# Power_Protection_DigitalAndAnalogInterfa.net
KiCad netlist of a schematic drawn in Altium Designer
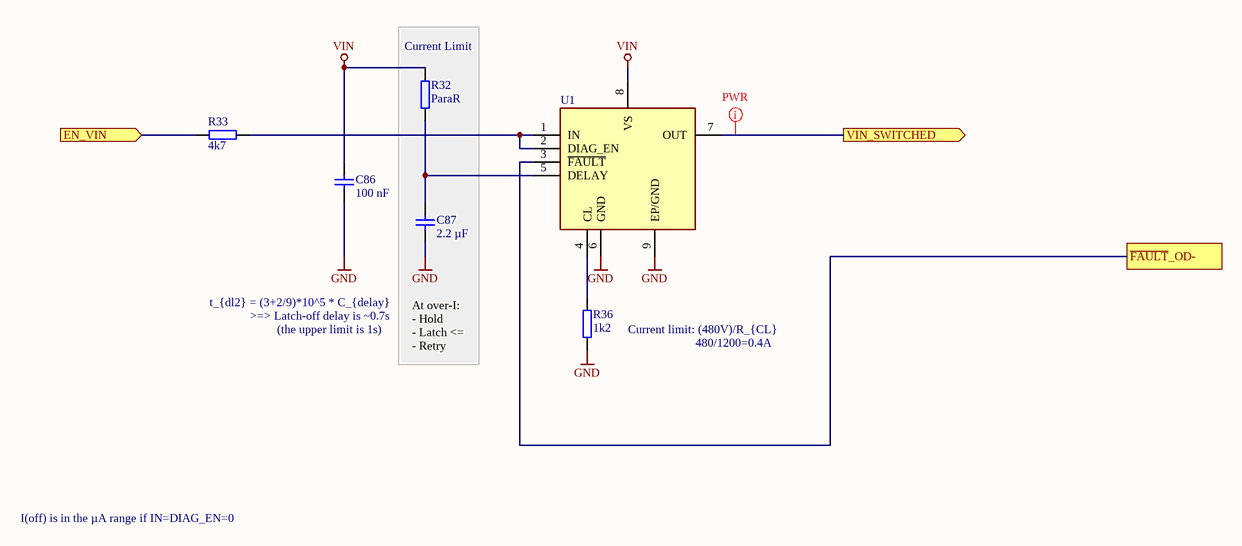
[diagram p0: Power_Protection_DigitalAndAnalogInterfaces.SchDoc]

(export (version "E")
  (design (tool "Eeschema 10.0.6"))
  (components
    (comp (ref "C86")
      (value "100 nF")
      (footprint "C_0603_TE")
      (description "Generic capacitor")
      (fields
        (field (name "MANUFACTURER PART NUMBER") "UZgen_C_0603_100nF_50V_X7R")
        (field (name "MANUFACTURER") "UZgen")
        (field (name "CREATED FROM") "AGeiger")
      )
      (libsource (lib "user") (part "CAP-NP"))
    )
    (comp (ref "C87")
      (value "2.2 µF")
      (footprint "C_0603_TE")
      (description "Generic capacitor")
      (fields
        (field (name "MANUFACTURER PART NUMBER") "UZgen_C_0603_2.2uF_50V_X7R")
        (field (name "MANUFACTURER") "UZgen")
        (field (name "CREATED FROM") "UZgenTool")
      )
      (libsource (lib "user") (part "CAP-NP"))
    )
    (comp (ref "R32")
      (value "ParaR")
      (footprint "R_0603_TE")
      (description "Generic resistor (parametric)")
      (fields
        (field (name "MANUFACTURER PART NUMBER") "UZgen_R_0603_ParaR")
        (field (name "MANUFACTURER") "UZgen")
        (field (name "CREATED FROM") "UZgenTool")
      )
      (libsource (lib "user") (part "RES"))
    )
    (comp (ref "R33")
      (value "4k7")
      (footprint "R_0603_TE")
      (description "Generic resistor")
      (fields
        (field (name "MANUFACTURER PART NUMBER") "UZgen_R_0603_4k7")
        (field (name "MANUFACTURER") "UZgen")
        (field (name "CREATED FROM") "UZgenTool")
      )
      (libsource (lib "user") (part "RES"))
    )
    (comp (ref "R36")
      (value "1k2")
      (footprint "R_0603_TE")
      (description "Generic resistor")
      (fields
        (field (name "MANUFACTURER PART NUMBER") "UZgen_R_0603_1k2")
        (field (name "MANUFACTURER") "UZgen")
        (field (name "CREATED FROM") "UZgenTool")
      )
      (libsource (lib "user") (part "RES"))
    )
    (comp (ref "U1")
      (value "TPS1H000AQDGNRQ1")
      (footprint "SOP65P490X110-9N")
      (fields
        (field (name "MANUFACTURER") "Texas Instruments")
        (field (name "LCSC PART NUMBER") "C2653764")
        (field (name "CREATED FROM") "FRosner")
      )
      (libsource (lib "user") (part "TPS1H000AQDGNRQ1"))
    )
  )
  (nets
    (net (code "1") (name "/EN_VIN") (class "Default")
      (node (ref "R33") (pin "1") (pinfunction "1_1") (pintype "passive"))
    )
    (net (code "2") (name "/VIN_SWITCHED") (class "Default")
      (node (ref "U1") (pin "7") (pinfunction "OUT_7") (pintype "passive"))
    )
    (net (code "3") (name "/~{FAULT}_OD-") (class "Default")
      (node (ref "U1") (pin "3") (pinfunction "~{FAULT}_3") (pintype "passive"))
    )
    (net (code "4") (name "GND") (class "Default")
      (node (ref "C86") (pin "1") (pinfunction "1_1") (pintype "passive"))
      (node (ref "C87") (pin "1") (pinfunction "1_1") (pintype "passive"))
      (node (ref "R36") (pin "1") (pinfunction "1_1") (pintype "passive"))
      (node (ref "U1") (pin "6") (pinfunction "GND_6") (pintype "passive"))
      (node (ref "U1") (pin "9") (pinfunction "EP/GND_9") (pintype "passive"))
    )
    (net (code "5") (name "Net-(U1-CL)") (class "Default")
      (node (ref "R36") (pin "2") (pinfunction "2_2") (pintype "passive"))
      (node (ref "U1") (pin "4") (pinfunction "CL_4") (pintype "passive"))
    )
    (net (code "6") (name "Net-(U1-DELAY)") (class "Default")
      (node (ref "C87") (pin "2") (pinfunction "2_2") (pintype "passive"))
      (node (ref "R32") (pin "1") (pinfunction "1_1") (pintype "passive"))
      (node (ref "U1") (pin "5") (pinfunction "DELAY_5") (pintype "passive"))
    )
    (net (code "7") (name "Net-(U1-DIAG_EN)") (class "Default")
      (node (ref "R33") (pin "2") (pinfunction "2_2") (pintype "passive"))
      (node (ref "U1") (pin "1") (pinfunction "IN_1") (pintype "passive"))
      (node (ref "U1") (pin "2") (pinfunction "DIAG_EN_2") (pintype "passive"))
    )
    (net (code "8") (name "VIN") (class "Default")
      (node (ref "C86") (pin "2") (pinfunction "2_2") (pintype "passive"))
      (node (ref "R32") (pin "2") (pinfunction "2_2") (pintype "passive"))
      (node (ref "U1") (pin "8") (pinfunction "VS_8") (pintype "passive"))
    )
  )
)
